# src_md.net
KiCad netlist of a schematic drawn in EAGLE
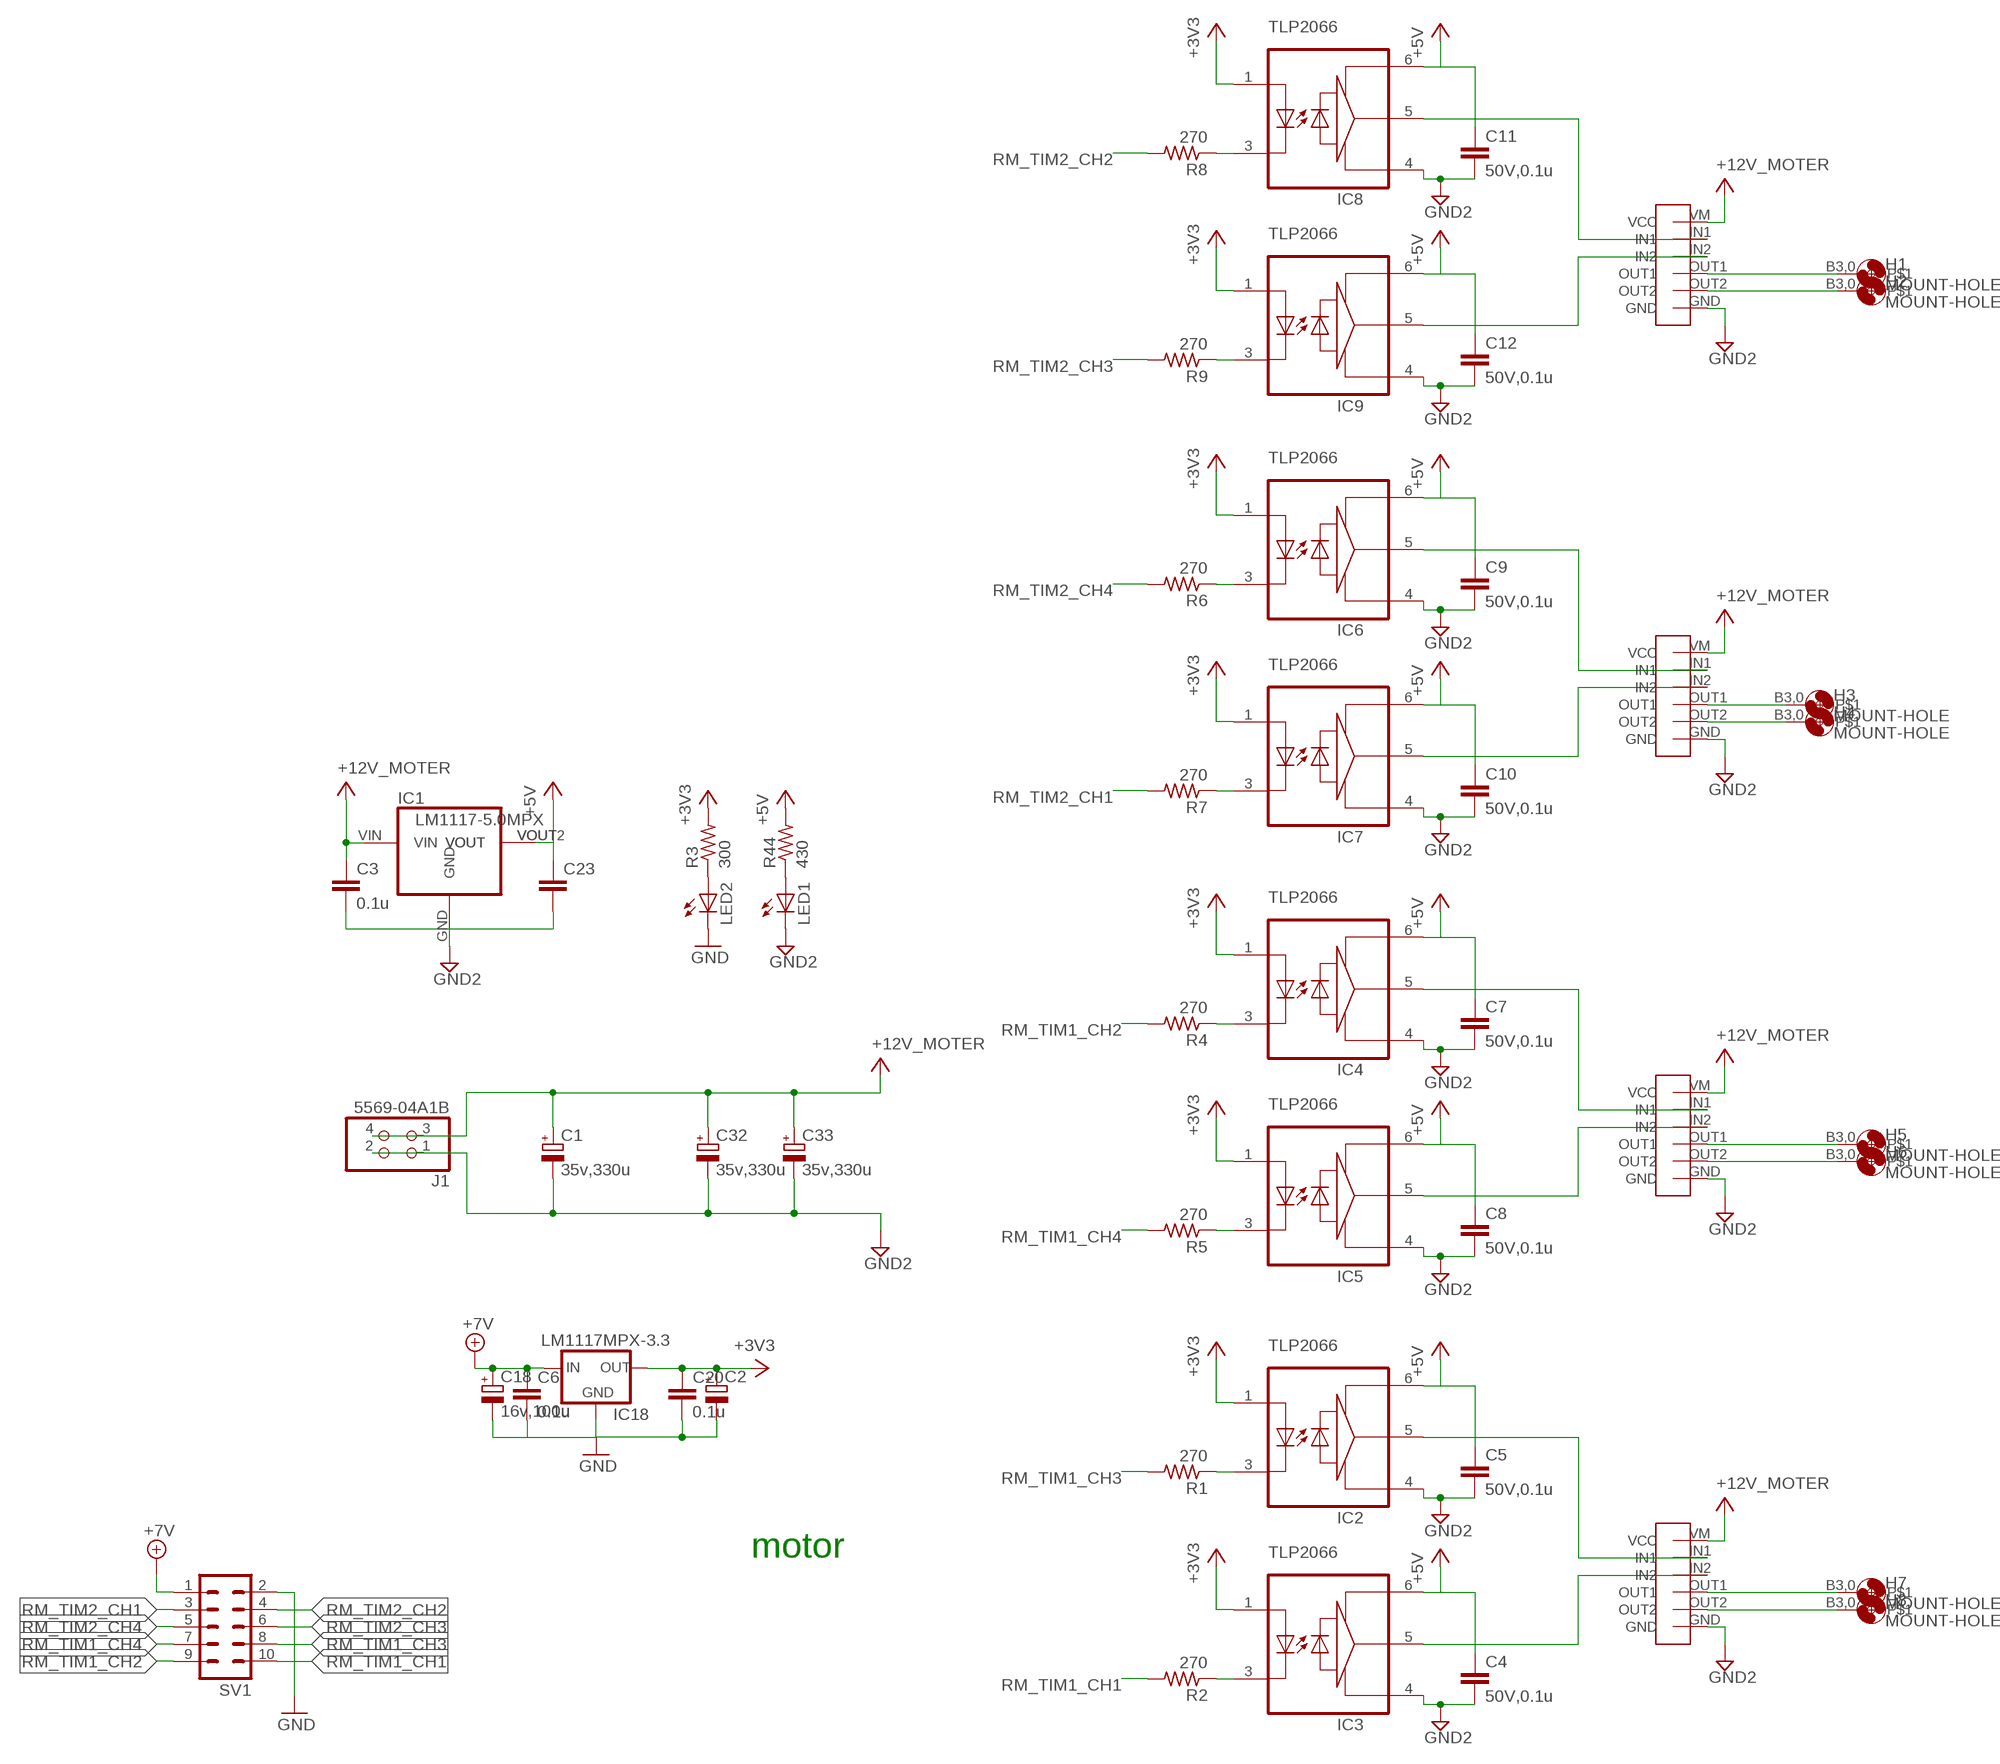
[diagram p0: schematic, sheet 1]

(export (version "E")
  (design (tool "Eeschema 10.0.6"))
  (components
    (comp (ref "C1")
      (value "35v,330u")
      (footprint "eagle-import:153CLV-1010")
      (libsource (lib "eagle-import") (part "CPOL-EU153CLV-1010"))
    )
    (comp (ref "C2")
      (value "CPOL-EU153CLV-0505")
      (footprint "eagle-import:153CLV-0505")
      (libsource (lib "eagle-import") (part "CPOL-EU153CLV-0505"))
    )
    (comp (ref "C3")
      (value "0.1u")
      (footprint "eagle-import:C0603K")
      (libsource (lib "eagle-import") (part "resistor_C-EUC0603K"))
    )
    (comp (ref "C4")
      (value "50V,0.1u")
      (footprint "eagle-import:C0603")
      (libsource (lib "eagle-import") (part "C-EUC0603"))
    )
    (comp (ref "C5")
      (value "50V,0.1u")
      (footprint "eagle-import:C0603")
      (libsource (lib "eagle-import") (part "C-EUC0603"))
    )
    (comp (ref "C6")
      (value "0.1u")
      (footprint "eagle-import:C0603")
      (libsource (lib "eagle-import") (part "C-EUC0603"))
    )
    (comp (ref "C7")
      (value "50V,0.1u")
      (footprint "eagle-import:C0603")
      (libsource (lib "eagle-import") (part "C-EUC0603"))
    )
    (comp (ref "C8")
      (value "50V,0.1u")
      (footprint "eagle-import:C0603")
      (libsource (lib "eagle-import") (part "C-EUC0603"))
    )
    (comp (ref "C9")
      (value "50V,0.1u")
      (footprint "eagle-import:C0603")
      (libsource (lib "eagle-import") (part "C-EUC0603"))
    )
    (comp (ref "C10")
      (value "50V,0.1u")
      (footprint "eagle-import:C0603")
      (libsource (lib "eagle-import") (part "C-EUC0603"))
    )
    (comp (ref "C11")
      (value "50V,0.1u")
      (footprint "eagle-import:C0603")
      (libsource (lib "eagle-import") (part "C-EUC0603"))
    )
    (comp (ref "C12")
      (value "50V,0.1u")
      (footprint "eagle-import:C0603")
      (libsource (lib "eagle-import") (part "C-EUC0603"))
    )
    (comp (ref "C18")
      (value "16v,100u")
      (footprint "eagle-import:153CLV-0605")
      (libsource (lib "eagle-import") (part "CPOL-EU153CLV-0605"))
    )
    (comp (ref "C20")
      (value "0.1u")
      (footprint "eagle-import:C0603K")
      (libsource (lib "eagle-import") (part "resistor_C-EUC0603K"))
    )
    (comp (ref "C23")
      (value "C-EUC0603K")
      (footprint "eagle-import:C0603K")
      (libsource (lib "eagle-import") (part "resistor_C-EUC0603K"))
    )
    (comp (ref "C32")
      (value "35v,330u")
      (footprint "eagle-import:153CLV-1010")
      (libsource (lib "eagle-import") (part "CPOL-EU153CLV-1010"))
    )
    (comp (ref "C33")
      (value "35v,330u")
      (footprint "eagle-import:153CLV-1010")
      (libsource (lib "eagle-import") (part "CPOL-EU153CLV-1010"))
    )
    (comp (ref "H1")
      (value "MOUNT-HOLE")
      (footprint "eagle-import:3,0-PAD")
      (libsource (lib "eagle-import") (part "MOUNT-HOLE"))
    )
    (comp (ref "H2")
      (value "MOUNT-HOLE")
      (footprint "eagle-import:3,0-PAD")
      (libsource (lib "eagle-import") (part "MOUNT-HOLE"))
    )
    (comp (ref "H3")
      (value "MOUNT-HOLE")
      (footprint "eagle-import:3,0-PAD")
      (libsource (lib "eagle-import") (part "MOUNT-HOLE"))
    )
    (comp (ref "H4")
      (value "MOUNT-HOLE")
      (footprint "eagle-import:3,0-PAD")
      (libsource (lib "eagle-import") (part "MOUNT-HOLE"))
    )
    (comp (ref "H5")
      (value "MOUNT-HOLE")
      (footprint "eagle-import:3,0-PAD")
      (libsource (lib "eagle-import") (part "MOUNT-HOLE"))
    )
    (comp (ref "H6")
      (value "MOUNT-HOLE")
      (footprint "eagle-import:3,0-PAD")
      (libsource (lib "eagle-import") (part "MOUNT-HOLE"))
    )
    (comp (ref "H7")
      (value "MOUNT-HOLE")
      (footprint "eagle-import:3,0-PAD")
      (libsource (lib "eagle-import") (part "MOUNT-HOLE"))
    )
    (comp (ref "H8")
      (value "MOUNT-HOLE")
      (footprint "eagle-import:3,0-PAD")
      (libsource (lib "eagle-import") (part "MOUNT-HOLE"))
    )
    (comp (ref "IC1")
      (value "LM1117-5.0MPX")
      (footprint "eagle-import:SOT223")
      (libsource (lib "eagle-import") (part "LM1117IMP-5.0"))
    )
    (comp (ref "IC2")
      (value "TLP2066")
      (footprint "eagle-import:MFSOP6")
      (libsource (lib "eagle-import") (part "TLP117"))
    )
    (comp (ref "IC3")
      (value "TLP2066")
      (footprint "eagle-import:MFSOP6")
      (libsource (lib "eagle-import") (part "TLP117"))
    )
    (comp (ref "IC4")
      (value "TLP2066")
      (footprint "eagle-import:MFSOP6")
      (libsource (lib "eagle-import") (part "TLP117"))
    )
    (comp (ref "IC5")
      (value "TLP2066")
      (footprint "eagle-import:MFSOP6")
      (libsource (lib "eagle-import") (part "TLP117"))
    )
    (comp (ref "IC6")
      (value "TLP2066")
      (footprint "eagle-import:MFSOP6")
      (libsource (lib "eagle-import") (part "TLP117"))
    )
    (comp (ref "IC7")
      (value "TLP2066")
      (footprint "eagle-import:MFSOP6")
      (libsource (lib "eagle-import") (part "TLP117"))
    )
    (comp (ref "IC8")
      (value "TLP2066")
      (footprint "eagle-import:MFSOP6")
      (libsource (lib "eagle-import") (part "TLP117"))
    )
    (comp (ref "IC9")
      (value "TLP2066")
      (footprint "eagle-import:MFSOP6")
      (libsource (lib "eagle-import") (part "TLP117"))
    )
    (comp (ref "IC18")
      (value "LM1117MPX-3.3")
      (footprint "eagle-import:SOT223")
      (libsource (lib "eagle-import") (part "LM1117"))
    )
    (comp (ref "J1")
      (value "5569-04A1B")
      (footprint "eagle-import:5569-04A1_2")
      (libsource (lib "eagle-import") (part "5569-04A1B"))
    )
    (comp (ref "LED1")
      (value "LEDCHIPLED_1206")
      (footprint "eagle-import:CHIPLED_1206")
      (libsource (lib "eagle-import") (part "LEDCHIPLED_1206"))
    )
    (comp (ref "LED2")
      (value "LEDCHIPLED_1206")
      (footprint "eagle-import:CHIPLED_1206")
      (libsource (lib "eagle-import") (part "LEDCHIPLED_1206"))
    )
    (comp (ref "R1")
      (value "270")
      (footprint "eagle-import:R0603")
      (libsource (lib "eagle-import") (part "resistor_R-US_R0603"))
    )
    (comp (ref "R2")
      (value "270")
      (footprint "eagle-import:R0603")
      (libsource (lib "eagle-import") (part "resistor_R-US_R0603"))
    )
    (comp (ref "R3")
      (value "300")
      (footprint "eagle-import:M2012")
      (libsource (lib "eagle-import") (part "R-US_M2012"))
    )
    (comp (ref "R4")
      (value "270")
      (footprint "eagle-import:R0603")
      (libsource (lib "eagle-import") (part "resistor_R-US_R0603"))
    )
    (comp (ref "R5")
      (value "270")
      (footprint "eagle-import:R0603")
      (libsource (lib "eagle-import") (part "resistor_R-US_R0603"))
    )
    (comp (ref "R6")
      (value "270")
      (footprint "eagle-import:R0603")
      (libsource (lib "eagle-import") (part "resistor_R-US_R0603"))
    )
    (comp (ref "R7")
      (value "270")
      (footprint "eagle-import:R0603")
      (libsource (lib "eagle-import") (part "resistor_R-US_R0603"))
    )
    (comp (ref "R8")
      (value "270")
      (footprint "eagle-import:R0603")
      (libsource (lib "eagle-import") (part "resistor_R-US_R0603"))
    )
    (comp (ref "R9")
      (value "270")
      (footprint "eagle-import:R0603")
      (libsource (lib "eagle-import") (part "resistor_R-US_R0603"))
    )
    (comp (ref "R44")
      (value "430")
      (footprint "eagle-import:M2012")
      (libsource (lib "eagle-import") (part "R-US_M2012"))
    )
    (comp (ref "SV1")
      (value "ML10L10PIN_T")
      (footprint "eagle-import:ML10L")
      (libsource (lib "eagle-import") (part "ML10L10PIN_T"))
    )
    (comp (ref "U$1")
      (value "TB6643")
      (footprint "eagle-import:TB6643")
      (libsource (lib "eagle-import") (part "TB6643"))
    )
    (comp (ref "U$2")
      (value "TB6643")
      (footprint "eagle-import:TB6643")
      (libsource (lib "eagle-import") (part "TB6643"))
    )
    (comp (ref "U$3")
      (value "TB6643")
      (footprint "eagle-import:TB6643")
      (libsource (lib "eagle-import") (part "TB6643"))
    )
    (comp (ref "U$4")
      (value "TB6643")
      (footprint "eagle-import:TB6643")
      (libsource (lib "eagle-import") (part "TB6643"))
    )
  )
  (nets
    (net (code "1") (name "+3V3") (class "Default")
      (node (ref "C2") (pin "+") (pinfunction "+_+") (pintype "passive"))
      (node (ref "C20") (pin "1") (pinfunction "1_1") (pintype "passive"))
      (node (ref "IC18") (pin "2") (pinfunction "OUT1_2") (pintype "passive"))
      (node (ref "IC18") (pin "4") (pinfunction "OUT_4") (pintype "passive"))
      (node (ref "IC2") (pin "1") (pinfunction "1_1") (pintype "input"))
      (node (ref "IC3") (pin "1") (pinfunction "1_1") (pintype "input"))
      (node (ref "IC4") (pin "1") (pinfunction "1_1") (pintype "input"))
      (node (ref "IC5") (pin "1") (pinfunction "1_1") (pintype "input"))
      (node (ref "IC6") (pin "1") (pinfunction "1_1") (pintype "input"))
      (node (ref "IC7") (pin "1") (pinfunction "1_1") (pintype "input"))
      (node (ref "IC8") (pin "1") (pinfunction "1_1") (pintype "input"))
      (node (ref "IC9") (pin "1") (pinfunction "1_1") (pintype "input"))
      (node (ref "R3") (pin "2") (pinfunction "2_2") (pintype "passive"))
    )
    (net (code "2") (name "+5V") (class "Default")
      (node (ref "C10") (pin "1") (pinfunction "1_1") (pintype "passive"))
      (node (ref "C11") (pin "1") (pinfunction "1_1") (pintype "passive"))
      (node (ref "C12") (pin "1") (pinfunction "1_1") (pintype "passive"))
      (node (ref "C23") (pin "1") (pinfunction "1_1") (pintype "passive"))
      (node (ref "C4") (pin "1") (pinfunction "1_1") (pintype "passive"))
      (node (ref "C5") (pin "1") (pinfunction "1_1") (pintype "passive"))
      (node (ref "C7") (pin "1") (pinfunction "1_1") (pintype "passive"))
      (node (ref "C8") (pin "1") (pinfunction "1_1") (pintype "passive"))
      (node (ref "C9") (pin "1") (pinfunction "1_1") (pintype "passive"))
      (node (ref "IC1") (pin "VOUT") (pinfunction "VOUT_VOUT") (pintype "output"))
      (node (ref "IC1") (pin "VOUT2") (pinfunction "VOUT_VOUT2") (pintype "output"))
      (node (ref "IC2") (pin "6") (pinfunction "VCC_6") (pintype "power_in"))
      (node (ref "IC3") (pin "6") (pinfunction "VCC_6") (pintype "power_in"))
      (node (ref "IC4") (pin "6") (pinfunction "VCC_6") (pintype "power_in"))
      (node (ref "IC5") (pin "6") (pinfunction "VCC_6") (pintype "power_in"))
      (node (ref "IC6") (pin "6") (pinfunction "VCC_6") (pintype "power_in"))
      (node (ref "IC7") (pin "6") (pinfunction "VCC_6") (pintype "power_in"))
      (node (ref "IC8") (pin "6") (pinfunction "VCC_6") (pintype "power_in"))
      (node (ref "IC9") (pin "6") (pinfunction "VCC_6") (pintype "power_in"))
      (node (ref "R44") (pin "2") (pinfunction "2_2") (pintype "passive"))
    )
    (net (code "3") (name "+7V") (class "Default")
      (node (ref "C18") (pin "+") (pinfunction "+_+") (pintype "passive"))
      (node (ref "C6") (pin "1") (pinfunction "1_1") (pintype "passive"))
      (node (ref "IC18") (pin "3") (pinfunction "IN_3") (pintype "input"))
      (node (ref "SV1") (pin "1") (pinfunction "1_1") (pintype "passive"))
    )
    (net (code "4") (name "+12V_MOTER") (class "Default")
      (node (ref "C1") (pin "+") (pinfunction "+_+") (pintype "passive"))
      (node (ref "C3") (pin "1") (pinfunction "1_1") (pintype "passive"))
      (node (ref "C32") (pin "+") (pinfunction "+_+") (pintype "passive"))
      (node (ref "C33") (pin "+") (pinfunction "+_+") (pintype "passive"))
      (node (ref "IC1") (pin "VIN") (pinfunction "VIN_VIN") (pintype "input"))
      (node (ref "J1") (pin "3") (pinfunction "3_3") (pintype "passive"))
      (node (ref "J1") (pin "4") (pinfunction "4_4") (pintype "passive"))
      (node (ref "U$1") (pin "VM") (pinfunction "VCC_VM") (pintype "bidirectional"))
      (node (ref "U$2") (pin "VM") (pinfunction "VCC_VM") (pintype "bidirectional"))
      (node (ref "U$3") (pin "VM") (pinfunction "VCC_VM") (pintype "bidirectional"))
      (node (ref "U$4") (pin "VM") (pinfunction "VCC_VM") (pintype "bidirectional"))
    )
    (net (code "5") (name "GND") (class "Default")
      (node (ref "C18") (pin "-") (pinfunction "-_-") (pintype "passive"))
      (node (ref "C2") (pin "-") (pinfunction "-_-") (pintype "passive"))
      (node (ref "C20") (pin "2") (pinfunction "2_2") (pintype "passive"))
      (node (ref "C6") (pin "2") (pinfunction "2_2") (pintype "passive"))
      (node (ref "IC18") (pin "1") (pinfunction "GND_1") (pintype "input"))
      (node (ref "LED2") (pin "C") (pinfunction "C_C") (pintype "passive"))
      (node (ref "SV1") (pin "2") (pinfunction "2_2") (pintype "passive"))
    )
    (net (code "6") (name "GND2") (class "Default")
      (node (ref "C1") (pin "-") (pinfunction "-_-") (pintype "passive"))
      (node (ref "C10") (pin "2") (pinfunction "2_2") (pintype "passive"))
      (node (ref "C11") (pin "2") (pinfunction "2_2") (pintype "passive"))
      (node (ref "C12") (pin "2") (pinfunction "2_2") (pintype "passive"))
      (node (ref "C23") (pin "2") (pinfunction "2_2") (pintype "passive"))
      (node (ref "C3") (pin "2") (pinfunction "2_2") (pintype "passive"))
      (node (ref "C32") (pin "-") (pinfunction "-_-") (pintype "passive"))
      (node (ref "C33") (pin "-") (pinfunction "-_-") (pintype "passive"))
      (node (ref "C4") (pin "2") (pinfunction "2_2") (pintype "passive"))
      (node (ref "C5") (pin "2") (pinfunction "2_2") (pintype "passive"))
      (node (ref "C7") (pin "2") (pinfunction "2_2") (pintype "passive"))
      (node (ref "C8") (pin "2") (pinfunction "2_2") (pintype "passive"))
      (node (ref "C9") (pin "2") (pinfunction "2_2") (pintype "passive"))
      (node (ref "IC1") (pin "GND") (pinfunction "GND_GND") (pintype "power_in"))
      (node (ref "IC2") (pin "4") (pinfunction "GND_4") (pintype "power_in"))
      (node (ref "IC3") (pin "4") (pinfunction "GND_4") (pintype "power_in"))
      (node (ref "IC4") (pin "4") (pinfunction "GND_4") (pintype "power_in"))
      (node (ref "IC5") (pin "4") (pinfunction "GND_4") (pintype "power_in"))
      (node (ref "IC6") (pin "4") (pinfunction "GND_4") (pintype "power_in"))
      (node (ref "IC7") (pin "4") (pinfunction "GND_4") (pintype "power_in"))
      (node (ref "IC8") (pin "4") (pinfunction "GND_4") (pintype "power_in"))
      (node (ref "IC9") (pin "4") (pinfunction "GND_4") (pintype "power_in"))
      (node (ref "J1") (pin "1") (pinfunction "1_1") (pintype "passive"))
      (node (ref "J1") (pin "2") (pinfunction "2_2") (pintype "passive"))
      (node (ref "LED1") (pin "C") (pinfunction "C_C") (pintype "passive"))
      (node (ref "U$1") (pin "GND") (pinfunction "GND_GND") (pintype "bidirectional"))
      (node (ref "U$2") (pin "GND") (pinfunction "GND_GND") (pintype "bidirectional"))
      (node (ref "U$3") (pin "GND") (pinfunction "GND_GND") (pintype "bidirectional"))
      (node (ref "U$4") (pin "GND") (pinfunction "GND_GND") (pintype "bidirectional"))
    )
    (net (code "7") (name "Net-(H1-P$1)") (class "Default")
      (node (ref "H1") (pin "B3,0") (pinfunction "P$1_B3,0") (pintype "bidirectional"))
      (node (ref "U$4") (pin "OUT1") (pinfunction "OUT1_OUT1") (pintype "bidirectional"))
    )
    (net (code "8") (name "Net-(H2-P$1)") (class "Default")
      (node (ref "H2") (pin "B3,0") (pinfunction "P$1_B3,0") (pintype "bidirectional"))
      (node (ref "U$4") (pin "OUT2") (pinfunction "OUT2_OUT2") (pintype "bidirectional"))
    )
    (net (code "9") (name "Net-(H3-P$1)") (class "Default")
      (node (ref "H3") (pin "B3,0") (pinfunction "P$1_B3,0") (pintype "bidirectional"))
      (node (ref "U$3") (pin "OUT1") (pinfunction "OUT1_OUT1") (pintype "bidirectional"))
    )
    (net (code "10") (name "Net-(H4-P$1)") (class "Default")
      (node (ref "H4") (pin "B3,0") (pinfunction "P$1_B3,0") (pintype "bidirectional"))
      (node (ref "U$3") (pin "OUT2") (pinfunction "OUT2_OUT2") (pintype "bidirectional"))
    )
    (net (code "11") (name "Net-(H5-P$1)") (class "Default")
      (node (ref "H5") (pin "B3,0") (pinfunction "P$1_B3,0") (pintype "bidirectional"))
      (node (ref "U$2") (pin "OUT1") (pinfunction "OUT1_OUT1") (pintype "bidirectional"))
    )
    (net (code "12") (name "Net-(H6-P$1)") (class "Default")
      (node (ref "H6") (pin "B3,0") (pinfunction "P$1_B3,0") (pintype "bidirectional"))
      (node (ref "U$2") (pin "OUT2") (pinfunction "OUT2_OUT2") (pintype "bidirectional"))
    )
    (net (code "13") (name "Net-(H7-P$1)") (class "Default")
      (node (ref "H7") (pin "B3,0") (pinfunction "P$1_B3,0") (pintype "bidirectional"))
      (node (ref "U$1") (pin "OUT1") (pinfunction "OUT1_OUT1") (pintype "bidirectional"))
    )
    (net (code "14") (name "Net-(H8-P$1)") (class "Default")
      (node (ref "H8") (pin "B3,0") (pinfunction "P$1_B3,0") (pintype "bidirectional"))
      (node (ref "U$1") (pin "OUT2") (pinfunction "OUT2_OUT2") (pintype "bidirectional"))
    )
    (net (code "15") (name "Net-(IC2-Pad3)") (class "Default")
      (node (ref "IC2") (pin "3") (pinfunction "3_3") (pintype "output"))
      (node (ref "R1") (pin "1") (pinfunction "1_1") (pintype "passive"))
    )
    (net (code "16") (name "Net-(IC2-Pad5)") (class "Default")
      (node (ref "IC2") (pin "5") (pinfunction "5_5") (pintype "output"))
      (node (ref "U$1") (pin "IN1") (pinfunction "IN1_IN1") (pintype "bidirectional"))
    )
    (net (code "17") (name "Net-(IC3-Pad3)") (class "Default")
      (node (ref "IC3") (pin "3") (pinfunction "3_3") (pintype "output"))
      (node (ref "R2") (pin "1") (pinfunction "1_1") (pintype "passive"))
    )
    (net (code "18") (name "Net-(IC3-Pad5)") (class "Default")
      (node (ref "IC3") (pin "5") (pinfunction "5_5") (pintype "output"))
      (node (ref "U$1") (pin "IN2") (pinfunction "IN2_IN2") (pintype "bidirectional"))
    )
    (net (code "19") (name "Net-(IC4-Pad3)") (class "Default")
      (node (ref "IC4") (pin "3") (pinfunction "3_3") (pintype "output"))
      (node (ref "R4") (pin "1") (pinfunction "1_1") (pintype "passive"))
    )
    (net (code "20") (name "Net-(IC4-Pad5)") (class "Default")
      (node (ref "IC4") (pin "5") (pinfunction "5_5") (pintype "output"))
      (node (ref "U$2") (pin "IN1") (pinfunction "IN1_IN1") (pintype "bidirectional"))
    )
    (net (code "21") (name "Net-(IC5-Pad3)") (class "Default")
      (node (ref "IC5") (pin "3") (pinfunction "3_3") (pintype "output"))
      (node (ref "R5") (pin "1") (pinfunction "1_1") (pintype "passive"))
    )
    (net (code "22") (name "Net-(IC5-Pad5)") (class "Default")
      (node (ref "IC5") (pin "5") (pinfunction "5_5") (pintype "output"))
      (node (ref "U$2") (pin "IN2") (pinfunction "IN2_IN2") (pintype "bidirectional"))
    )
    (net (code "23") (name "Net-(IC6-Pad3)") (class "Default")
      (node (ref "IC6") (pin "3") (pinfunction "3_3") (pintype "output"))
      (node (ref "R6") (pin "1") (pinfunction "1_1") (pintype "passive"))
    )
    (net (code "24") (name "Net-(IC6-Pad5)") (class "Default")
      (node (ref "IC6") (pin "5") (pinfunction "5_5") (pintype "output"))
      (node (ref "U$3") (pin "IN1") (pinfunction "IN1_IN1") (pintype "bidirectional"))
    )
    (net (code "25") (name "Net-(IC7-Pad3)") (class "Default")
      (node (ref "IC7") (pin "3") (pinfunction "3_3") (pintype "output"))
      (node (ref "R7") (pin "1") (pinfunction "1_1") (pintype "passive"))
    )
    (net (code "26") (name "Net-(IC7-Pad5)") (class "Default")
      (node (ref "IC7") (pin "5") (pinfunction "5_5") (pintype "output"))
      (node (ref "U$3") (pin "IN2") (pinfunction "IN2_IN2") (pintype "bidirectional"))
    )
    (net (code "27") (name "Net-(IC8-Pad3)") (class "Default")
      (node (ref "IC8") (pin "3") (pinfunction "3_3") (pintype "output"))
      (node (ref "R8") (pin "1") (pinfunction "1_1") (pintype "passive"))
    )
    (net (code "28") (name "Net-(IC8-Pad5)") (class "Default")
      (node (ref "IC8") (pin "5") (pinfunction "5_5") (pintype "output"))
      (node (ref "U$4") (pin "IN1") (pinfunction "IN1_IN1") (pintype "bidirectional"))
    )
    (net (code "29") (name "Net-(IC9-Pad3)") (class "Default")
      (node (ref "IC9") (pin "3") (pinfunction "3_3") (pintype "output"))
      (node (ref "R9") (pin "1") (pinfunction "1_1") (pintype "passive"))
    )
    (net (code "30") (name "Net-(IC9-Pad5)") (class "Default")
      (node (ref "IC9") (pin "5") (pinfunction "5_5") (pintype "output"))
      (node (ref "U$4") (pin "IN2") (pinfunction "IN2_IN2") (pintype "bidirectional"))
    )
    (net (code "31") (name "Net-(LED1-PadA)") (class "Default")
      (node (ref "LED1") (pin "A") (pinfunction "A_A") (pintype "passive"))
      (node (ref "R44") (pin "1") (pinfunction "1_1") (pintype "passive"))
    )
    (net (code "32") (name "Net-(LED2-PadA)") (class "Default")
      (node (ref "LED2") (pin "A") (pinfunction "A_A") (pintype "passive"))
      (node (ref "R3") (pin "1") (pinfunction "1_1") (pintype "passive"))
    )
    (net (code "33") (name "RM_TIM1_CH1") (class "Default")
      (node (ref "R2") (pin "2") (pinfunction "2_2") (pintype "passive"))
      (node (ref "SV1") (pin "10") (pinfunction "10_10") (pintype "passive"))
    )
    (net (code "34") (name "RM_TIM1_CH2") (class "Default")
      (node (ref "R4") (pin "2") (pinfunction "2_2") (pintype "passive"))
      (node (ref "SV1") (pin "9") (pinfunction "9_9") (pintype "passive"))
    )
    (net (code "35") (name "RM_TIM1_CH3") (class "Default")
      (node (ref "R1") (pin "2") (pinfunction "2_2") (pintype "passive"))
      (node (ref "SV1") (pin "8") (pinfunction "8_8") (pintype "passive"))
    )
    (net (code "36") (name "RM_TIM1_CH4") (class "Default")
      (node (ref "R5") (pin "2") (pinfunction "2_2") (pintype "passive"))
      (node (ref "SV1") (pin "7") (pinfunction "7_7") (pintype "passive"))
    )
    (net (code "37") (name "RM_TIM2_CH1") (class "Default")
      (node (ref "R7") (pin "2") (pinfunction "2_2") (pintype "passive"))
      (node (ref "SV1") (pin "3") (pinfunction "3_3") (pintype "passive"))
    )
    (net (code "38") (name "RM_TIM2_CH2") (class "Default")
      (node (ref "R8") (pin "2") (pinfunction "2_2") (pintype "passive"))
      (node (ref "SV1") (pin "4") (pinfunction "4_4") (pintype "passive"))
    )
    (net (code "39") (name "RM_TIM2_CH3") (class "Default")
      (node (ref "R9") (pin "2") (pinfunction "2_2") (pintype "passive"))
      (node (ref "SV1") (pin "6") (pinfunction "6_6") (pintype "passive"))
    )
    (net (code "40") (name "RM_TIM2_CH4") (class "Default")
      (node (ref "R6") (pin "2") (pinfunction "2_2") (pintype "passive"))
      (node (ref "SV1") (pin "5") (pinfunction "5_5") (pintype "passive"))
    )
  )
)
